# SoC_FPGA_HD_84_87.net
KiCad netlist of a schematic drawn in Altium Designer
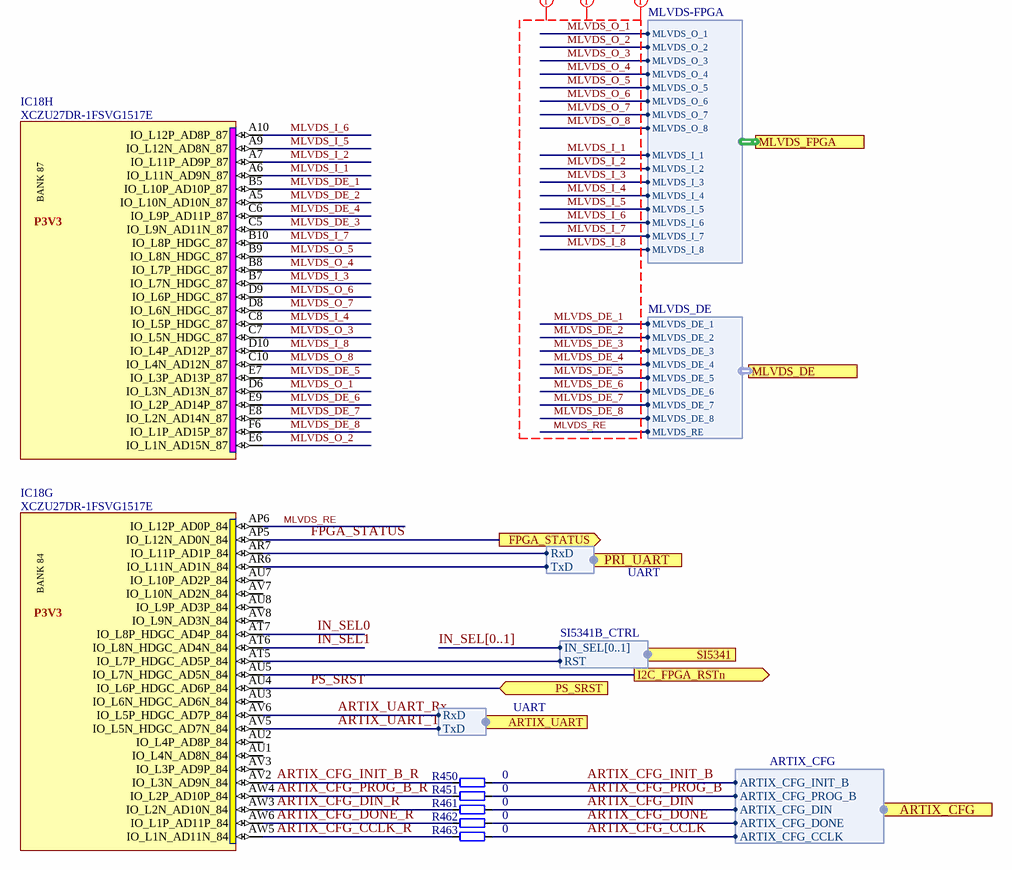
[diagram p0: SoC_FPGA_HD_84_87.SchDoc]

(export (version "E")
  (design (tool "Eeschema 10.0.6"))
  (components
    (comp (ref "IC18")
      (value "XCZU27DR-1FSVG1517E")
      (footprint "XILINX_FSVG1517 (XCZU27DR)")
      (fields (field (name "MANUFACTURER") "XILINX") (field (name "AUTHOR") "CERN DEM MR"))
      (libsource (lib "ICs And Semiconductors") (part "XCZU27DR-1FSVG1517E"))
    )
    (comp (ref "R450")
      (value "0")
      (footprint "RESC1005X40N")
      (description "Resistor")
      (fields
        (field (name "MANUFACTURER PART NUMBER") "R0402_0R_JUMPER")
        (field (name "MANUFACTURER") "GENERIC")
        (field (name "AUTHOR") "CERN DEM JLC")
      )
      (libsource (lib "Resistors") (part "Resistor"))
    )
    (comp (ref "R451")
      (value "0")
      (footprint "RESC1005X40N")
      (description "Resistor")
      (fields
        (field (name "MANUFACTURER PART NUMBER") "R0402_0R_JUMPER")
        (field (name "MANUFACTURER") "GENERIC")
        (field (name "AUTHOR") "CERN DEM JLC")
      )
      (libsource (lib "Resistors") (part "Resistor"))
    )
    (comp (ref "R461")
      (value "0")
      (footprint "RESC1005X40N")
      (description "Resistor")
      (fields
        (field (name "MANUFACTURER PART NUMBER") "R0402_0R_JUMPER")
        (field (name "MANUFACTURER") "GENERIC")
        (field (name "AUTHOR") "CERN DEM JLC")
      )
      (libsource (lib "Resistors") (part "Resistor"))
    )
    (comp (ref "R462")
      (value "0")
      (footprint "RESC1005X40N")
      (description "Resistor")
      (fields
        (field (name "MANUFACTURER PART NUMBER") "R0402_0R_JUMPER")
        (field (name "MANUFACTURER") "GENERIC")
        (field (name "AUTHOR") "CERN DEM JLC")
      )
      (libsource (lib "Resistors") (part "Resistor"))
    )
    (comp (ref "R463")
      (value "0")
      (footprint "RESC1005X40N")
      (description "Resistor")
      (fields
        (field (name "MANUFACTURER PART NUMBER") "R0402_0R_JUMPER")
        (field (name "MANUFACTURER") "GENERIC")
        (field (name "AUTHOR") "CERN DEM JLC")
      )
      (libsource (lib "Resistors") (part "Resistor"))
    )
  )
  (nets
    (net (code "6") (name "/ARTIX_CFG_CCLK") (class "Default")
      (node (ref "R463") (pin "2") (pinfunction "2_2") (pintype "passive"))
    )
    (net (code "7") (name "/ARTIX_CFG_CCLK_R") (class "Default")
      (node (ref "IC18") (pin "AW5") (pinfunction "IO_L1N_AD11N_84_AW5") (pintype "bidirectional"))
      (node (ref "R463") (pin "1") (pinfunction "1_1") (pintype "passive"))
    )
    (net (code "8") (name "/ARTIX_CFG_DIN") (class "Default")
      (node (ref "R461") (pin "2") (pinfunction "2_2") (pintype "passive"))
    )
    (net (code "9") (name "/ARTIX_CFG_DIN_R") (class "Default")
      (node (ref "IC18") (pin "AW3") (pinfunction "IO_L2N_AD10N_84_AW3") (pintype "bidirectional"))
      (node (ref "R461") (pin "1") (pinfunction "1_1") (pintype "passive"))
    )
    (net (code "10") (name "/ARTIX_CFG_DONE") (class "Default")
      (node (ref "R462") (pin "2") (pinfunction "2_2") (pintype "passive"))
    )
    (net (code "11") (name "/ARTIX_CFG_DONE_R") (class "Default")
      (node (ref "IC18") (pin "AW6") (pinfunction "IO_L1P_AD11P_84_AW6") (pintype "bidirectional"))
      (node (ref "R462") (pin "1") (pinfunction "1_1") (pintype "passive"))
    )
    (net (code "12") (name "/ARTIX_CFG_INIT_B") (class "Default")
      (node (ref "R450") (pin "2") (pinfunction "2_2") (pintype "passive"))
    )
    (net (code "13") (name "/ARTIX_CFG_INIT_B_R") (class "Default")
      (node (ref "IC18") (pin "AV2") (pinfunction "IO_L3N_AD9N_84_AV2") (pintype "bidirectional"))
      (node (ref "R450") (pin "1") (pinfunction "1_1") (pintype "passive"))
    )
    (net (code "14") (name "/ARTIX_CFG_PROG_B") (class "Default")
      (node (ref "R451") (pin "2") (pinfunction "2_2") (pintype "passive"))
    )
    (net (code "15") (name "/ARTIX_CFG_PROG_B_R") (class "Default")
      (node (ref "IC18") (pin "AW4") (pinfunction "IO_L2P_AD10P_84_AW4") (pintype "bidirectional"))
      (node (ref "R451") (pin "1") (pinfunction "1_1") (pintype "passive"))
    )
    (net (code "16") (name "/ARTIX_UART_Rx") (class "Default")
      (node (ref "IC18") (pin "AV6") (pinfunction "IO_L5P_HDGC_AD7P_84_AV6") (pintype "bidirectional"))
    )
    (net (code "17") (name "/ARTIX_UART_Tx") (class "Default")
      (node (ref "IC18") (pin "AV5") (pinfunction "IO_L5N_HDGC_AD7N_84_AV5") (pintype "bidirectional"))
    )
    (net (code "18") (name "/FPGA_STATUS") (class "Default")
      (node (ref "IC18") (pin "AP5") (pinfunction "IO_L12N_AD0N_84_AP5") (pintype "bidirectional"))
    )
    (net (code "19") (name "/I2C_FPGA_RSTn") (class "Default")
      (node (ref "IC18") (pin "AU5") (pinfunction "IO_L7N_HDGC_AD5N_84_AU5") (pintype "bidirectional"))
    )
    (net (code "20") (name "/IN_SEL0") (class "Default")
      (node (ref "IC18") (pin "AT7") (pinfunction "IO_L8P_HDGC_AD4P_84_AT7") (pintype "bidirectional"))
    )
    (net (code "21") (name "/IN_SEL1") (class "Default")
      (node (ref "IC18") (pin "AT6") (pinfunction "IO_L8N_HDGC_AD4N_84_AT6") (pintype "bidirectional"))
    )
    (net (code "22") (name "/MLVDS_DE_1") (class "Default")
      (node (ref "IC18") (pin "B5") (pinfunction "IO_L10P_AD10P_87_B5") (pintype "bidirectional"))
    )
    (net (code "23") (name "/MLVDS_DE_2") (class "Default")
      (node (ref "IC18") (pin "A5") (pinfunction "IO_L10N_AD10N_87_A5") (pintype "bidirectional"))
    )
    (net (code "24") (name "/MLVDS_DE_3") (class "Default")
      (node (ref "IC18") (pin "C5") (pinfunction "IO_L9N_AD11N_87_C5") (pintype "bidirectional"))
    )
    (net (code "25") (name "/MLVDS_DE_4") (class "Default")
      (node (ref "IC18") (pin "C6") (pinfunction "IO_L9P_AD11P_87_C6") (pintype "bidirectional"))
    )
    (net (code "26") (name "/MLVDS_DE_5") (class "Default")
      (node (ref "IC18") (pin "E7") (pinfunction "IO_L3P_AD13P_87_E7") (pintype "bidirectional"))
    )
    (net (code "27") (name "/MLVDS_DE_6") (class "Default")
      (node (ref "IC18") (pin "E9") (pinfunction "IO_L2P_AD14P_87_E9") (pintype "bidirectional"))
    )
    (net (code "28") (name "/MLVDS_DE_7") (class "Default")
      (node (ref "IC18") (pin "E8") (pinfunction "IO_L2N_AD14N_87_E8") (pintype "bidirectional"))
    )
    (net (code "29") (name "/MLVDS_DE_8") (class "Default")
      (node (ref "IC18") (pin "F6") (pinfunction "IO_L1P_AD15P_87_F6") (pintype "bidirectional"))
    )
    (net (code "30") (name "/MLVDS_I_1") (class "Default")
      (node (ref "IC18") (pin "A6") (pinfunction "IO_L11N_AD9N_87_A6") (pintype "bidirectional"))
    )
    (net (code "31") (name "/MLVDS_I_2") (class "Default")
      (node (ref "IC18") (pin "A7") (pinfunction "IO_L11P_AD9P_87_A7") (pintype "bidirectional"))
    )
    (net (code "32") (name "/MLVDS_I_3") (class "Default")
      (node (ref "IC18") (pin "B7") (pinfunction "IO_L7N_HDGC_87_B7") (pintype "bidirectional"))
    )
    (net (code "33") (name "/MLVDS_I_4") (class "Default")
      (node (ref "IC18") (pin "C8") (pinfunction "IO_L5P_HDGC_87_C8") (pintype "bidirectional"))
    )
    (net (code "34") (name "/MLVDS_I_5") (class "Default")
      (node (ref "IC18") (pin "A9") (pinfunction "IO_L12N_AD8N_87_A9") (pintype "bidirectional"))
    )
    (net (code "35") (name "/MLVDS_I_6") (class "Default")
      (node (ref "IC18") (pin "A10") (pinfunction "IO_L12P_AD8P_87_A10") (pintype "bidirectional"))
    )
    (net (code "36") (name "/MLVDS_I_7") (class "Default")
      (node (ref "IC18") (pin "B10") (pinfunction "IO_L8P_HDGC_87_B10") (pintype "bidirectional"))
    )
    (net (code "37") (name "/MLVDS_I_8") (class "Default")
      (node (ref "IC18") (pin "D10") (pinfunction "IO_L4P_AD12P_87_D10") (pintype "bidirectional"))
    )
    (net (code "38") (name "/MLVDS_O_1") (class "Default")
      (node (ref "IC18") (pin "D6") (pinfunction "IO_L3N_AD13N_87_D6") (pintype "bidirectional"))
    )
    (net (code "39") (name "/MLVDS_O_2") (class "Default")
      (node (ref "IC18") (pin "E6") (pinfunction "IO_L1N_AD15N_87_E6") (pintype "bidirectional"))
    )
    (net (code "40") (name "/MLVDS_O_3") (class "Default")
      (node (ref "IC18") (pin "C7") (pinfunction "IO_L5N_HDGC_87_C7") (pintype "bidirectional"))
    )
    (net (code "41") (name "/MLVDS_O_4") (class "Default")
      (node (ref "IC18") (pin "B8") (pinfunction "IO_L7P_HDGC_87_B8") (pintype "bidirectional"))
    )
    (net (code "42") (name "/MLVDS_O_5") (class "Default")
      (node (ref "IC18") (pin "B9") (pinfunction "IO_L8N_HDGC_87_B9") (pintype "bidirectional"))
    )
    (net (code "43") (name "/MLVDS_O_6") (class "Default")
      (node (ref "IC18") (pin "D9") (pinfunction "IO_L6P_HDGC_87_D9") (pintype "bidirectional"))
    )
    (net (code "44") (name "/MLVDS_O_7") (class "Default")
      (node (ref "IC18") (pin "D8") (pinfunction "IO_L6N_HDGC_87_D8") (pintype "bidirectional"))
    )
    (net (code "45") (name "/MLVDS_O_8") (class "Default")
      (node (ref "IC18") (pin "C10") (pinfunction "IO_L4N_AD12N_87_C10") (pintype "bidirectional"))
    )
    (net (code "46") (name "/MLVDS_RE") (class "Default")
      (node (ref "IC18") (pin "AP6") (pinfunction "IO_L12P_AD0P_84_AP6") (pintype "bidirectional"))
    )
    (net (code "47") (name "/PS_SRST") (class "Default")
      (node (ref "IC18") (pin "AU4") (pinfunction "IO_L6P_HDGC_AD6P_84_AU4") (pintype "bidirectional"))
    )
    (net (code "48") (name "/RST") (class "Default")
      (node (ref "IC18") (pin "AT5") (pinfunction "IO_L7P_HDGC_AD5P_84_AT5") (pintype "bidirectional"))
    )
    (net (code "55") (name "unconnected-(IC18G-IO_L3P_AD9P_84-PadAV3)") (class "Default")
      (node (ref "IC18") (pin "AV3") (pinfunction "IO_L3P_AD9P_84_AV3") (pintype "bidirectional"))
    )
    (net (code "56") (name "unconnected-(IC18G-IO_L4N_AD8N_84-PadAU1)") (class "Default")
      (node (ref "IC18") (pin "AU1") (pinfunction "IO_L4N_AD8N_84_AU1") (pintype "bidirectional"))
    )
    (net (code "57") (name "unconnected-(IC18G-IO_L4P_AD8P_84-PadAU2)") (class "Default")
      (node (ref "IC18") (pin "AU2") (pinfunction "IO_L4P_AD8P_84_AU2") (pintype "bidirectional"))
    )
    (net (code "58") (name "unconnected-(IC18G-IO_L6N_HDGC_AD6N_84-PadAU3)") (class "Default")
      (node (ref "IC18") (pin "AU3") (pinfunction "IO_L6N_HDGC_AD6N_84_AU3") (pintype "bidirectional"))
    )
    (net (code "59") (name "unconnected-(IC18G-IO_L9N_AD3N_84-PadAV8)") (class "Default")
      (node (ref "IC18") (pin "AV8") (pinfunction "IO_L9N_AD3N_84_AV8") (pintype "bidirectional"))
    )
    (net (code "60") (name "unconnected-(IC18G-IO_L9P_AD3P_84-PadAU8)") (class "Default")
      (node (ref "IC18") (pin "AU8") (pinfunction "IO_L9P_AD3P_84_AU8") (pintype "bidirectional"))
    )
    (net (code "61") (name "unconnected-(IC18G-IO_L10N_AD2N_84-PadAV7)") (class "Default")
      (node (ref "IC18") (pin "AV7") (pinfunction "IO_L10N_AD2N_84_AV7") (pintype "bidirectional"))
    )
    (net (code "62") (name "unconnected-(IC18G-IO_L10P_AD2P_84-PadAU7)") (class "Default")
      (node (ref "IC18") (pin "AU7") (pinfunction "IO_L10P_AD2P_84_AU7") (pintype "bidirectional"))
    )
    (net (code "63") (name "unconnected-(IC18G-IO_L11N_AD1N_84-PadAR6)") (class "Default")
      (node (ref "IC18") (pin "AR6") (pinfunction "IO_L11N_AD1N_84_AR6") (pintype "bidirectional"))
    )
    (net (code "64") (name "unconnected-(IC18G-IO_L11P_AD1P_84-PadAR7)") (class "Default")
      (node (ref "IC18") (pin "AR7") (pinfunction "IO_L11P_AD1P_84_AR7") (pintype "bidirectional"))
    )
  )
)
